# 2_FLYBACK_AUXILIAR.net
KiCad netlist of a schematic drawn in Altium Designer
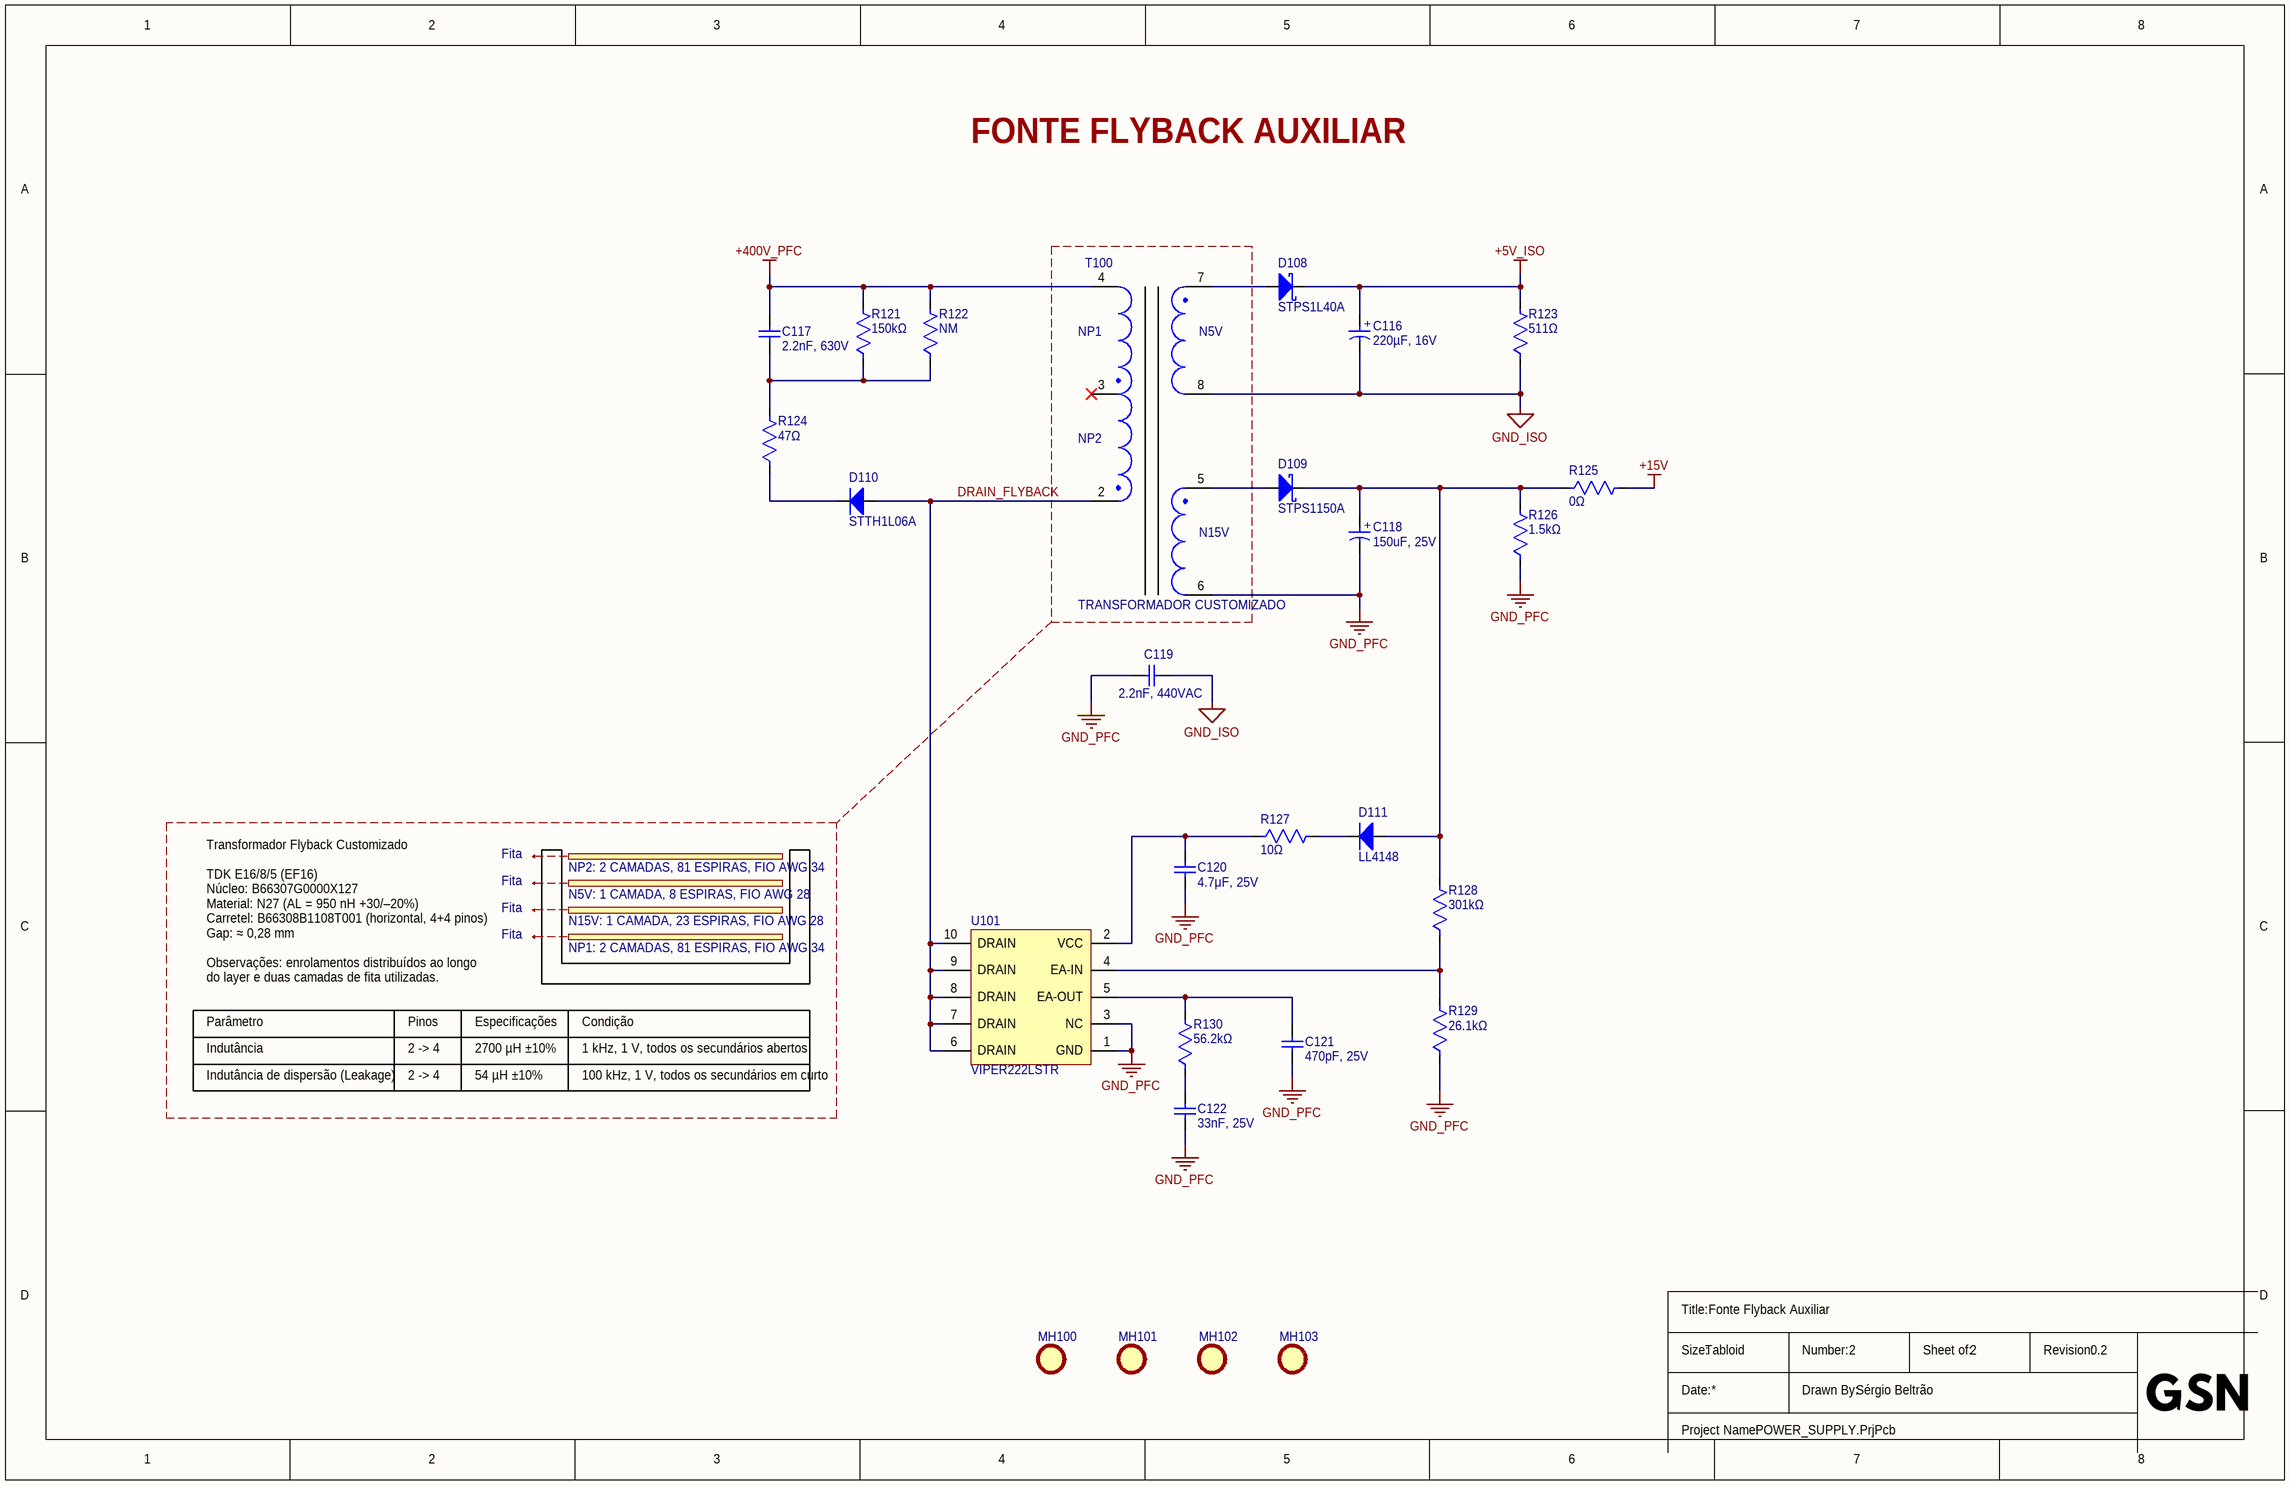
[diagram p0: 2_FLYBACK_AUXILIAR.SchDoc]

(export (version "E")
  (design (tool "Eeschema 10.0.6"))
  (components
    (comp (ref "C116")
      (value "220µF, 16V")
      (footprint "WCAP-ATUL_D8H11.5")
      (description "WCAP-ATUL Aluminum Electrolytic Capacitor, Radial, THT, 8mm x 11.5mm, 220µF, 16V")
      (fields
        (field (name "MANUFACTURER PART NUMBER") "860040374004")
        (field (name "MANUFACTURER") "Wurth Elektronik")
      )
      (libsource (lib "WE - Passive Components") (part "Capacitor_Polarized"))
    )
    (comp (ref "C117")
      (value "2.2nF, 630V")
      (footprint "WCAP-CSMH_1206_H1.6")
      (fields
        (field (name "MANUFACTURER PART NUMBER") "885342008007")
        (field (name "MANUFACTURER") "Wurth Elektronik")
      )
      (libsource (lib "WE - Passive Components") (part "Capacitor_Non-Polarized"))
    )
    (comp (ref "C118")
      (value "150uF, 25V")
      (footprint "WCAP-ATLI_D8H11.5")
      (description "WCAP-ATLI Aluminum Electrolytic Capacitor, Radial, THT, D8 x H11.5mm, 150µF, 25V")
      (fields
        (field (name "MANUFACTURER PART NUMBER") "860080474008")
        (field (name "MANUFACTURER") "Wurth Elektronik")
      )
      (libsource (lib "WE - Passive Components") (part "Capacitor_Polarized"))
    )
    (comp (ref "C119")
      (value "2.2nF, 440VAC")
      (footprint "CAP_5US63V7_VIS")
      (description "CAP CER 2200PF 440VAC Y5U RADIAL")
      (fields
        (field (name "MANUFACTURER") "Vishay")
        (field (name "MANUFACTURER PART NUMBER") "VY2222M35Y5US63V7")
      )
      (libsource (lib "Capacitors-PTH-Ceramic") (part "VY2222M35Y5US63V7"))
    )
    (comp (ref "C120")
      (value "4.7μF, 25V")
      (footprint "WCAP-CSGP_0805_L2W1.25H1.25")
      (description "WCAP-CSGP Multilayer Ceramic Chip Capacitor, General Purpose, size 0805, 4.7μF, 25V")
      (fields
        (field (name "MANUFACTURER PART NUMBER") "885012107018")
        (field (name "MANUFACTURER") "Wurth Elektronik")
      )
      (libsource (lib "WE - Passive Components") (part "Capacitor_Non-Polarized"))
    )
    (comp (ref "C121")
      (value "470pF, 25V")
      (footprint "WCAP-CSGP_0603_L1.6W0.8H0.8_Wave")
      (description "WCAP-CSGP Multilayer Ceramic Chip Capacitor, General Purpose, size 0603, 470pF, 25V")
      (fields
        (field (name "MANUFACTURER PART NUMBER") "885012006042")
        (field (name "MANUFACTURER") "Wurth Elektronik")
      )
      (libsource (lib "WE - Passive Components") (part "Capacitor_Non-Polarized"))
    )
    (comp (ref "C122")
      (value "33nF, 25V")
      (footprint "WCAP-CSGP_0603_L1.6W0.8H0.8_Wave")
      (description "WCAP-CSGP Multilayer Ceramic Chip Capacitor, General Purpose, size 0603, 33nF, 25V")
      (fields
        (field (name "MANUFACTURER PART NUMBER") "885012206068")
        (field (name "MANUFACTURER") "Wurth Elektronik")
      )
      (libsource (lib "WE - Passive Components") (part "Capacitor_Non-Polarized"))
    )
    (comp (ref "D108")
      (value "STPS1L40A")
      (footprint "SMA")
      (description "DIODE SCHOTTKY 40V 1A DO214AC")
      (fields (field (name "MANUFACTURER") "STMicroelectronics"))
      (libsource (lib "Diodes") (part "STPS1L40A"))
    )
    (comp (ref "D109")
      (value "STPS1150A")
      (footprint "SMA")
      (description "DIODE SCHOTTKY 150V 1A SMA")
      (fields (field (name "MANUFACTURER") "STMicroelectronics"))
      (libsource (lib "Diodes") (part "STPS1150A"))
    )
    (comp (ref "D110")
      (value "STTH1L06A")
      (footprint "SMA")
      (description "DIODE STANDARD 600V 1A SMA")
      (fields (field (name "MANUFACTURER") "STMicroelectronics"))
      (libsource (lib "Diodes") (part "STTH1L06A"))
    )
    (comp (ref "D111")
      (value "LL4148")
      (footprint "SOD-80-DIODE")
      (description "DIODE STANDARD 100V 200MA SOD80")
      (fields (field (name "MANUFACTURER") "onsemi") (field (name "VOLTAGE") "100V"))
      (libsource (lib "Diodes") (part "LL4148"))
    )
    (comp (ref "MH100")
      (value "Mounting Hole 2.5mm")
      (footprint "MOUNTING_HOLE_M2P5_UNPLATED")
      (description "UNPLATED MOUNTING HOLE WITH 2.5MM DIAMETER")
      (libsource (lib "Electro-Mechanical") (part "MTH-2P5MM-UNPLATED"))
    )
    (comp (ref "MH101")
      (value "Mounting Hole 2.5mm")
      (footprint "MOUNTING_HOLE_M2P5_UNPLATED")
      (description "UNPLATED MOUNTING HOLE WITH 2.5MM DIAMETER")
      (libsource (lib "Electro-Mechanical") (part "MTH-2P5MM-UNPLATED"))
    )
    (comp (ref "MH102")
      (value "Mounting Hole 2.5mm")
      (footprint "MOUNTING_HOLE_M2P5_UNPLATED")
      (description "UNPLATED MOUNTING HOLE WITH 2.5MM DIAMETER")
      (libsource (lib "Electro-Mechanical") (part "MTH-2P5MM-UNPLATED"))
    )
    (comp (ref "MH103")
      (value "Mounting Hole 2.5mm")
      (footprint "MOUNTING_HOLE_M2P5_UNPLATED")
      (description "UNPLATED MOUNTING HOLE WITH 2.5MM DIAMETER")
      (libsource (lib "Electro-Mechanical") (part "MTH-2P5MM-UNPLATED"))
    )
    (comp (ref "R121")
      (value "150kΩ")
      (footprint "2010-WAVE")
      (description "RES 150K OHM 1% 3/4W 2010")
      (fields
        (field (name "MANUFACTURER") "Yageo Group")
        (field (name "MANUFACTURER PART NUMBER") "RC2010FK-07150KL")
      )
      (libsource (lib "Resistors-2010-E96-Yageo") (part "RC2010FK-07150KL"))
    )
    (comp (ref "R122")
      (value "NM")
      (footprint "2010-WAVE")
      (description "RES 150K OHM 1% 3/4W 2010")
      (fields
        (field (name "MANUFACTURER") "Yageo Group")
        (field (name "MANUFACTURER PART NUMBER") "RC2010FK-07150KL")
      )
      (libsource (lib "Resistors-2010-E96-Yageo") (part "RC2010FK-07150KL"))
    )
    (comp (ref "R123")
      (value "511Ω")
      (footprint "1206-WAVE")
      (description "RES 511 OHM 1% 1/4W 1206")
      (fields
        (field (name "MANUFACTURER") "Yageo Group")
        (field (name "MANUFACTURER PART NUMBER") "RC1206FR-07511RL")
      )
      (libsource (lib "Resistors-1206-E96-Yageo") (part "RC1206FR-07511RL"))
    )
    (comp (ref "R124")
      (value "47Ω")
      (footprint "1206-WAVE")
      (description "RES 47R OHM 1% 1/4W 1206")
      (fields
        (field (name "MANUFACTURER") "Yageo Group")
        (field (name "MANUFACTURER PART NUMBER") "RC1206FR-0747RL")
      )
      (libsource (lib "Resistors-1206-E96-Yageo") (part "RC1206FR-0747RL"))
    )
    (comp (ref "R125")
      (value "0Ω")
      (footprint "1206-WAVE")
      (description "RES 0 OHM JUMPER 1/4W 1206")
      (fields
        (field (name "MANUFACTURER") "Yageo Group")
        (field (name "MANUFACTURER PART NUMBER") "RC1206FR-070RL")
      )
      (libsource (lib "Resistors-1206-E96-Yageo") (part "RC1206FR-070RL"))
    )
    (comp (ref "R126")
      (value "1.5kΩ")
      (footprint "1206-WAVE")
      (description "RES 1.5K OHM 1% 1/4W 1206")
      (fields
        (field (name "MANUFACTURER") "Yageo Group")
        (field (name "MANUFACTURER PART NUMBER") "RC1206FR-071K5L")
      )
      (libsource (lib "Resistors-1206-E96-Yageo") (part "RC1206FR-071K5L"))
    )
    (comp (ref "R127")
      (value "10Ω")
      (footprint "0603-WAVE")
      (description "RES 10 OHM 1% 1/10W 0603")
      (fields
        (field (name "MANUFACTURER PART NUMBER") "RC0603FR-0710RL")
        (field (name "MANUFACTURER") "Yageo Group")
      )
      (libsource (lib "Resistors-0603-E96-Yageo") (part "RC0603FR-0710RL"))
    )
    (comp (ref "R128")
      (value "301kΩ")
      (footprint "0603-WAVE")
      (description "RES 301K OHM 1% 1/10W 0603")
      (fields
        (field (name "MANUFACTURER PART NUMBER") "RC0603FR-07301KL")
        (field (name "MANUFACTURER") "Yageo Group")
      )
      (libsource (lib "Resistors-0603-E96-Yageo") (part "RC0603FR-07301KL"))
    )
    (comp (ref "R129")
      (value "26.1kΩ")
      (footprint "0603-WAVE")
      (description "RES 26.1K OHM 1% 1/10W 0603")
      (fields
        (field (name "MANUFACTURER PART NUMBER") "RC0603FR-0726K1L")
        (field (name "MANUFACTURER") "Yageo Group")
      )
      (libsource (lib "Resistors-0603-E96-Yageo") (part "RC0603FR-0726K1L"))
    )
    (comp (ref "R130")
      (value "56.2kΩ")
      (footprint "0603-WAVE")
      (description "RES 56.2K OHM 1% 1/10W 0603")
      (fields
        (field (name "MANUFACTURER PART NUMBER") "RC0603FR-0756K2L")
        (field (name "MANUFACTURER") "Yageo Group")
      )
      (libsource (lib "Resistors-0603-E96-Yageo") (part "RC0603FR-0756K2L"))
    )
    (comp (ref "T100")
      (value "TRANSFORMADOR CUSTOMIZADO")
      (footprint "TDK_E_16_8_5")
      (description "TRANSFORMADOR FLYBACK CUSTOMIZADO QUE USEI NO TCC")
      (fields (field (name "MANUFACTURER PART NUMBER") "Custom"))
      (libsource (lib "Transformers") (part "CUSTOM_FLYBACK_TCC"))
    )
    (comp (ref "U101")
      (value "VIPER222LSTR")
      (footprint "SSOP-10")
      (description "IC OFFLINE SWITCH FLYBACK 10SSOP")
      (fields (field (name "MANUFACTURER") "STMicroelectronics"))
      (libsource (lib "Power-Management-ICs") (part "VIPER222LSTR"))
    )
  )
  (nets
    (net (code "1") (name "+5V_ISO") (class "Default")
      (node (ref "C116") (pin "1") (pinfunction "P_1") (pintype "passive"))
      (node (ref "D108") (pin "1") (pinfunction "K_1") (pintype "passive"))
      (node (ref "R123") (pin "2") (pinfunction "2_2") (pintype "passive"))
    )
    (net (code "2") (name "+15V") (class "Default")
      (node (ref "R125") (pin "2") (pinfunction "2_2") (pintype "passive"))
    )
    (net (code "3") (name "+400V_PFC") (class "Default")
      (node (ref "C117") (pin "2") (pinfunction "2_2") (pintype "passive"))
      (node (ref "R121") (pin "2") (pinfunction "2_2") (pintype "passive"))
      (node (ref "R122") (pin "2") (pinfunction "2_2") (pintype "passive"))
      (node (ref "T100") (pin "4") (pinfunction "4_4") (pintype "passive"))
    )
    (net (code "4") (name "/DRAIN_FLYBACK") (class "Default")
      (node (ref "D110") (pin "2") (pinfunction "A_2") (pintype "passive"))
      (node (ref "T100") (pin "2") (pinfunction "2_2") (pintype "passive"))
      (node (ref "U101") (pin "10") (pinfunction "DRAIN_10") (pintype "passive"))
      (node (ref "U101") (pin "6") (pinfunction "DRAIN_6") (pintype "passive"))
      (node (ref "U101") (pin "7") (pinfunction "DRAIN_7") (pintype "passive"))
      (node (ref "U101") (pin "8") (pinfunction "DRAIN_8") (pintype "passive"))
      (node (ref "U101") (pin "9") (pinfunction "DRAIN_9") (pintype "passive"))
    )
    (net (code "5") (name "GND_ISO") (class "Default")
      (node (ref "C116") (pin "2") (pinfunction "N_2") (pintype "passive"))
      (node (ref "C119") (pin "2") (pinfunction "2_2") (pintype "passive"))
      (node (ref "R123") (pin "1") (pinfunction "1_1") (pintype "passive"))
      (node (ref "T100") (pin "8") (pinfunction "8_8") (pintype "passive"))
    )
    (net (code "6") (name "GND_PFC") (class "Default")
      (node (ref "C118") (pin "2") (pinfunction "N_2") (pintype "passive"))
      (node (ref "C119") (pin "1") (pinfunction "1_1") (pintype "passive"))
      (node (ref "C120") (pin "1") (pinfunction "1_1") (pintype "passive"))
      (node (ref "C121") (pin "1") (pinfunction "1_1") (pintype "passive"))
      (node (ref "C122") (pin "1") (pinfunction "1_1") (pintype "passive"))
      (node (ref "R126") (pin "1") (pinfunction "1_1") (pintype "passive"))
      (node (ref "R129") (pin "1") (pinfunction "1_1") (pintype "passive"))
      (node (ref "T100") (pin "6") (pinfunction "6_6") (pintype "passive"))
      (node (ref "U101") (pin "1") (pinfunction "GND_1") (pintype "passive"))
      (node (ref "U101") (pin "3") (pinfunction "NC_3") (pintype "passive"))
    )
    (net (code "7") (name "Net-(C117-Pad1)") (class "Default")
      (node (ref "C117") (pin "1") (pinfunction "1_1") (pintype "passive"))
      (node (ref "R121") (pin "1") (pinfunction "1_1") (pintype "passive"))
      (node (ref "R122") (pin "1") (pinfunction "1_1") (pintype "passive"))
      (node (ref "R124") (pin "2") (pinfunction "2_2") (pintype "passive"))
    )
    (net (code "8") (name "Net-(C118-P)") (class "Default")
      (node (ref "C118") (pin "1") (pinfunction "P_1") (pintype "passive"))
      (node (ref "D109") (pin "1") (pinfunction "K_1") (pintype "passive"))
      (node (ref "D111") (pin "2") (pinfunction "A_2") (pintype "passive"))
      (node (ref "R125") (pin "1") (pinfunction "1_1") (pintype "passive"))
      (node (ref "R126") (pin "2") (pinfunction "2_2") (pintype "passive"))
      (node (ref "R128") (pin "2") (pinfunction "2_2") (pintype "passive"))
    )
    (net (code "9") (name "Net-(C122-Pad2)") (class "Default")
      (node (ref "C122") (pin "2") (pinfunction "2_2") (pintype "passive"))
      (node (ref "R130") (pin "1") (pinfunction "1_1") (pintype "passive"))
    )
    (net (code "10") (name "Net-(D108-A)") (class "Default")
      (node (ref "D108") (pin "2") (pinfunction "A_2") (pintype "passive"))
      (node (ref "T100") (pin "7") (pinfunction "7_7") (pintype "passive"))
    )
    (net (code "11") (name "Net-(D109-A)") (class "Default")
      (node (ref "D109") (pin "2") (pinfunction "A_2") (pintype "passive"))
      (node (ref "T100") (pin "5") (pinfunction "5_5") (pintype "passive"))
    )
    (net (code "12") (name "Net-(D110-K)") (class "Default")
      (node (ref "D110") (pin "1") (pinfunction "K_1") (pintype "passive"))
      (node (ref "R124") (pin "1") (pinfunction "1_1") (pintype "passive"))
    )
    (net (code "13") (name "Net-(D111-K)") (class "Default")
      (node (ref "D111") (pin "1") (pinfunction "K_1") (pintype "passive"))
      (node (ref "R127") (pin "2") (pinfunction "2_2") (pintype "passive"))
    )
    (net (code "14") (name "Net-(U101-EA-IN)") (class "Default")
      (node (ref "R128") (pin "1") (pinfunction "1_1") (pintype "passive"))
      (node (ref "R129") (pin "2") (pinfunction "2_2") (pintype "passive"))
      (node (ref "U101") (pin "4") (pinfunction "EA-IN_4") (pintype "passive"))
    )
    (net (code "15") (name "Net-(U101-EA-OUT)") (class "Default")
      (node (ref "C121") (pin "2") (pinfunction "2_2") (pintype "passive"))
      (node (ref "R130") (pin "2") (pinfunction "2_2") (pintype "passive"))
      (node (ref "U101") (pin "5") (pinfunction "EA-OUT_5") (pintype "passive"))
    )
    (net (code "16") (name "Net-(U101-VCC)") (class "Default")
      (node (ref "C120") (pin "2") (pinfunction "2_2") (pintype "passive"))
      (node (ref "R127") (pin "1") (pinfunction "1_1") (pintype "passive"))
      (node (ref "U101") (pin "2") (pinfunction "VCC_2") (pintype "passive"))
    )
    (net (code "17") (name "unconnected-(T100-Pad3)") (class "Default")
      (node (ref "T100") (pin "3") (pinfunction "3_3") (pintype "passive+no_connect"))
    )
  )
)
